# Supplies.net
KiCad netlist of a schematic drawn in Altium Designer
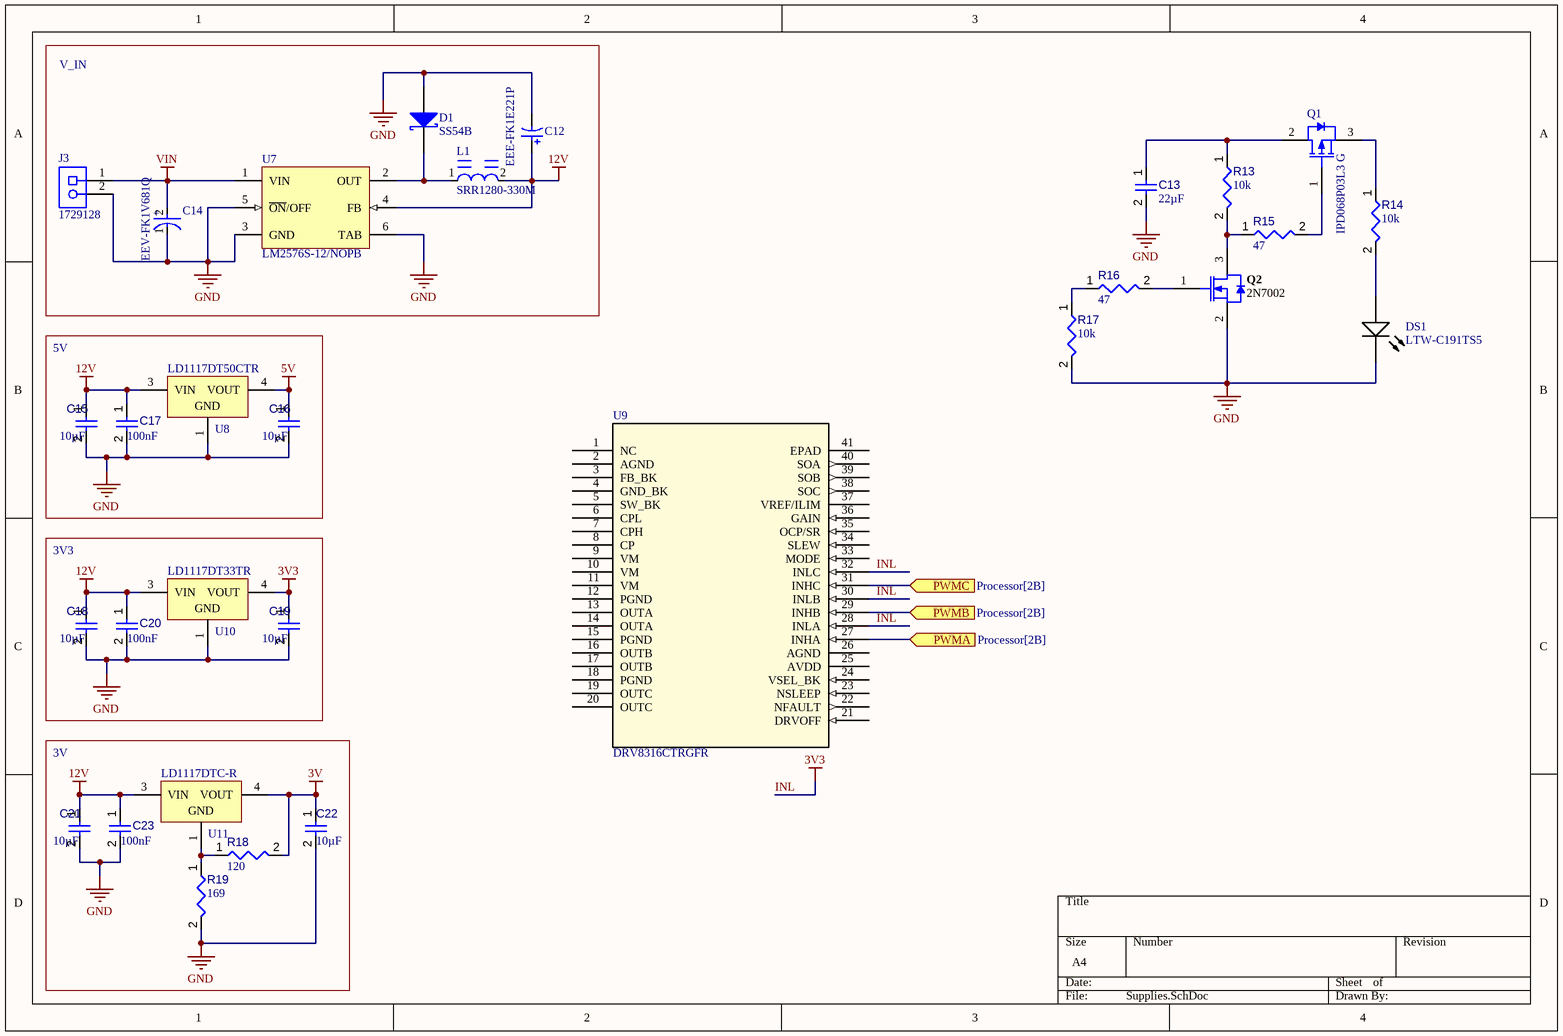
[diagram p0: Supplies.SchDoc]

(export (version "E")
  (design (tool "Eeschema 10.0.6"))
  (components
    (comp (ref "C12")
      (value "EEE-FK1E221P")
      (footprint "PNSC-EEE-FK1E221P_N")
      (fields (field (name "MANUFACTURER") "Panasonic"))
      (libsource (lib "Altium Content Vault") (part "CAP-P-2"))
    )
    (comp (ref "C13")
      (value "22µF")
      (footprint "CAPC0805(2012)145_L")
      (description "Chip Capacitor, 22µF +/-40%, 16V, 0805, Thickness 1.45 mm")
      (fields (field (name "TOLERANCE") "5%") (field (name "Comment") "Capacitor 22µF +/-40% 16V 0805"))
      (libsource (lib "UdeA") (part "CAP-NP-2"))
    )
    (comp (ref "C14")
      (value "EEV-FK1V681Q")
      (footprint "FP-FKH13-MFG")
      (description "CAP ALUM 680UF 20% 35V SMD")
      (fields (field (name "VOLTAGE") "35V") (field (name "TOLERANCE") "20%"))
      (libsource (lib "Altium Content Vault") (part "203bc49f2ac43e59fd269a8c329ed05"))
    )
    (comp (ref "C15")
      (value "10µF")
      (footprint "CAPC0805(2012)145_L")
      (description "Chip Capacitor, 22µF +/-40%, 16V, 0805, Thickness 1.45 mm")
      (fields (field (name "TOLERANCE") "5%") (field (name "Comment") "Capacitor 22µF +/-40% 16V 0805"))
      (libsource (lib "UdeA") (part "CAP-NP-2"))
    )
    (comp (ref "C16")
      (value "10µF")
      (footprint "CAPC0805(2012)145_L")
      (description "Chip Capacitor, 22µF +/-40%, 16V, 0805, Thickness 1.45 mm")
      (fields (field (name "TOLERANCE") "5%") (field (name "Comment") "Capacitor 22µF +/-40% 16V 0805"))
      (libsource (lib "UdeA") (part "CAP-NP-2"))
    )
    (comp (ref "C17")
      (value "100nF")
      (footprint "CAPC1608X90X40NL10T20")
      (description "Chip Capacitor, 100 nF, +/- 10%, 50 V, 0603 (1608 Metric)")
      (fields (field (name "TOLERANCE") "10%") (field (name "Comment") "Capacitor 100 nF +/-10% 50 V 0603"))
      (libsource (lib "UdeA") (part "CAP-NP-2"))
    )
    (comp (ref "C18")
      (value "10µF")
      (footprint "CAPC0805(2012)145_L")
      (description "Chip Capacitor, 22µF +/-40%, 16V, 0805, Thickness 1.45 mm")
      (fields (field (name "TOLERANCE") "5%") (field (name "Comment") "Capacitor 22µF +/-40% 16V 0805"))
      (libsource (lib "UdeA") (part "CAP-NP-2"))
    )
    (comp (ref "C19")
      (value "10µF")
      (footprint "CAPC0805(2012)145_L")
      (description "Chip Capacitor, 22µF +/-40%, 16V, 0805, Thickness 1.45 mm")
      (fields (field (name "TOLERANCE") "5%") (field (name "Comment") "Capacitor 22µF +/-40% 16V 0805"))
      (libsource (lib "UdeA") (part "CAP-NP-2"))
    )
    (comp (ref "C20")
      (value "100nF")
      (footprint "CAPC1608X90X40NL10T20")
      (description "Chip Capacitor, 100 nF, +/- 10%, 50 V, 0603 (1608 Metric)")
      (fields (field (name "TOLERANCE") "10%") (field (name "Comment") "Capacitor 100 nF +/-10% 50 V 0603"))
      (libsource (lib "UdeA") (part "CAP-NP-2"))
    )
    (comp (ref "C21")
      (value "10µF")
      (footprint "CAPC0805(2012)145_L")
      (description "Chip Capacitor, 22µF +/-40%, 16V, 0805, Thickness 1.45 mm")
      (fields (field (name "TOLERANCE") "5%") (field (name "Comment") "Capacitor 22µF +/-40% 16V 0805"))
      (libsource (lib "UdeA") (part "CAP-NP-2"))
    )
    (comp (ref "C22")
      (value "10µF")
      (footprint "CAPC0805(2012)145_L")
      (description "Chip Capacitor, 22µF +/-40%, 16V, 0805, Thickness 1.45 mm")
      (fields (field (name "TOLERANCE") "5%") (field (name "Comment") "Capacitor 22µF +/-40% 16V 0805"))
      (libsource (lib "UdeA") (part "CAP-NP-2"))
    )
    (comp (ref "C23")
      (value "100nF")
      (footprint "CAPC1608X90X40NL10T20")
      (description "Chip Capacitor, 100 nF, +/- 10%, 50 V, 0603 (1608 Metric)")
      (fields (field (name "TOLERANCE") "10%") (field (name "Comment") "Capacitor 100 nF +/-10% 50 V 0603"))
      (libsource (lib "UdeA") (part "CAP-NP-2"))
    )
    (comp (ref "D1")
      (value "SS54B")
      (footprint "JCET-SMB-2_M")
      (description "Schottky Barrier Rectifier, 40 V, 5 A, -55 to 150 degC, 2-Pin SMD")
      (fields (field (name "MANUFACTURER") "JCET"))
      (libsource (lib "Altium Content Vault") (part "DSKY-AK-2"))
    )
    (comp (ref "DS1")
      (value "LTW-C191TS5")
      (footprint "LTST-LTW-C191TS5_V")
      (description "LED Uni-Color White, 70 mW, 20 mA, -20 to 80 degC, 2-Pin SMD, RoHS, Tape and Reel")
      (fields (field (name "POWER") "70mW") (field (name "MANUFACTURER") "Lite-On"))
      (libsource (lib "UdeA") (part "LED-WHITE-AK-2"))
    )
    (comp (ref "J3")
      (value "1729128")
      (footprint "PHOE-1729128-2_V")
      (description "PCB Terminal Block, 13.5 A, 400 V, 2-Pin THD, RoHS, Bulk")
      (fields (field (name "MANUFACTURER") "Phoenix Contact"))
      (libsource (lib "Altium Content Vault") (part "CN-2P-F-R2"))
    )
    (comp (ref "L1")
      (value "SRR1280-330M")
      (footprint "FP-SRR1280-MFG")
      (description "FIXED IND 33UH 3.5A 57 MOHM SMD")
      (fields (field (name "TOLERANCE") "20%"))
      (libsource (lib "Altium Content Vault") (part "6d0fbef048cab01dc475e6ab11ab505"))
    )
    (comp (ref "Q1")
      (value "IPD068P03L3 G")
      (footprint "INF-PG-TO252-3-1_L")
      (fields (field (name "MANUFACTURER") "Infineon"))
      (libsource (lib "Altium Content Vault") (part "INF-PEMOS-GDS-3"))
    )
    (comp (ref "Q2")
      (value "2N7002")
      (footprint "INF-PG-SOT23_M")
      (fields (field (name "MANUFACTURER") "Infineon"))
      (libsource (lib "Altium Content Vault") (part "INF-NDMOS-GSD-3"))
    )
    (comp (ref "R13")
      (value "10k")
      (footprint "RESC1608X55X25ML10T15")
      (description "Chip Resistor, 10 KOhm, +/- 1%, 01 W, -55 to 155 degC, 0603 (1608 Metric)")
      (fields (field (name "POWER") "100mW") (field (name "TOLERANCE") "1%"))
      (libsource (lib "UdeA") (part "RES-2"))
    )
    (comp (ref "R14")
      (value "10k")
      (footprint "RESC1608X55X25ML10T15")
      (description "Chip Resistor, 10 KOhm, +/- 1%, 01 W, -55 to 155 degC, 0603 (1608 Metric)")
      (fields (field (name "POWER") "100mW") (field (name "TOLERANCE") "1%"))
      (libsource (lib "UdeA") (part "RES-2"))
    )
    (comp (ref "R15")
      (value "47")
      (footprint "RESC1608X55X25ML10T15")
      (description "Chip Resistor, 10 KOhm, +/- 1%, 01 W, -55 to 155 degC, 0603 (1608 Metric)")
      (fields (field (name "POWER") "100mW") (field (name "TOLERANCE") "1%"))
      (libsource (lib "UdeA") (part "RES-2"))
    )
    (comp (ref "R16")
      (value "47")
      (footprint "RESC1608X55X25ML10T15")
      (description "Chip Resistor, 10 KOhm, +/- 1%, 01 W, -55 to 155 degC, 0603 (1608 Metric)")
      (fields (field (name "POWER") "100mW") (field (name "TOLERANCE") "1%"))
      (libsource (lib "UdeA") (part "RES-2"))
    )
    (comp (ref "R17")
      (value "10k")
      (footprint "RESC1608X55X25ML10T15")
      (description "Chip Resistor, 10 KOhm, +/- 1%, 01 W, -55 to 155 degC, 0603 (1608 Metric)")
      (fields (field (name "POWER") "100mW") (field (name "TOLERANCE") "1%"))
      (libsource (lib "UdeA") (part "RES-2"))
    )
    (comp (ref "R18")
      (value "120")
      (footprint "RESC1608X55X25ML10T15")
      (description "Chip Resistor, 10 KOhm, +/- 1%, 01 W, -55 to 155 degC, 0603 (1608 Metric)")
      (fields (field (name "POWER") "100mW") (field (name "TOLERANCE") "1%"))
      (libsource (lib "UdeA") (part "RES-2"))
    )
    (comp (ref "R19")
      (value "169")
      (footprint "RESC1608X55X25ML10T15")
      (description "Chip Resistor, 10 KOhm, +/- 1%, 01 W, -55 to 155 degC, 0603 (1608 Metric)")
      (fields (field (name "POWER") "100mW") (field (name "TOLERANCE") "1%"))
      (libsource (lib "UdeA") (part "RES-2"))
    )
    (comp (ref "U7")
      (value "LM2576S-12/NOPB")
      (footprint "KTT0005B_N")
      (description "SIMPLE SWITCHER® 3A Step-Down Voltage Regulator, 5-pin TO-263, Pb-Free")
      (fields (field (name "MANUFACTURER") "Texas Instruments"))
      (libsource (lib "Altium Content Vault") (part "PM-REG-LM2575HVS-12"))
    )
    (comp (ref "U8")
      (value "LD1117DT50CTR")
      (footprint "TO-252_N")
      (description "Fixed Low Drop Positive Voltage Regulator, 5V, 3-Pin DPAK, Tape and Reel")
      (libsource (lib "Altium Content Vault") (part "PM-REG-LD1117-SOT3"))
    )
    (comp (ref "U9")
      (value "DRV8316CTRGFR")
      (footprint "VQFN40_RGF_TEX")
      (description "No Description Available")
      (fields (field (name "COPYRIGHT") "Copyright (C) 2024 Ultra Librarian. All rights reserved."))
      (libsource (lib "DRV8316CTRGFR") (part "DRV8316CTRGFR"))
    )
    (comp (ref "U10")
      (value "LD1117DT33TR")
      (footprint "TO-252_N")
      (description "Fixed Low Drop Positive Voltage Regulator, 3.3V, 3-Pin DPAK, Tape and Reel")
      (libsource (lib "Altium Content Vault") (part "PM-REG-LD1117-SOT3"))
    )
    (comp (ref "U11")
      (value "LD1117DTC-R")
      (footprint "TO-252_M")
      (description "Adjustable Low Drop Voltage Regulator, 1.25 to 15V, 3-Pin DPAK, Tape and Reel")
      (libsource (lib "Altium Content Vault") (part "PM-REG-LD1117-SOT3"))
    )
  )
  (nets
    (net (code "1") (name "/PWMA") (class "Default")
      (node (ref "U9") (pin "27") (pinfunction "INHA_27") (pintype "input"))
    )
    (net (code "2") (name "/PWMB") (class "Default")
      (node (ref "U9") (pin "29") (pinfunction "INHB_29") (pintype "input"))
    )
    (net (code "3") (name "/PWMC") (class "Default")
      (node (ref "U9") (pin "31") (pinfunction "INHC_31") (pintype "input"))
    )
    (net (code "4") (name "3V") (class "Default")
      (node (ref "C22") (pin "1") (pinfunction "1_1") (pintype "passive"))
      (node (ref "R18") (pin "2") (pinfunction "2_2") (pintype "passive"))
      (node (ref "U11") (pin "4") (pinfunction "VOUT_4") (pintype "power_in"))
    )
    (net (code "5") (name "3V3") (class "Default")
      (node (ref "C19") (pin "1") (pinfunction "1_1") (pintype "passive"))
      (node (ref "U10") (pin "4") (pinfunction "VOUT_4") (pintype "power_in"))
      (node (ref "U9") (pin "28") (pinfunction "INLA_28") (pintype "input"))
      (node (ref "U9") (pin "30") (pinfunction "INLB_30") (pintype "input"))
      (node (ref "U9") (pin "32") (pinfunction "INLC_32") (pintype "input"))
    )
    (net (code "6") (name "5V") (class "Default")
      (node (ref "C16") (pin "1") (pinfunction "1_1") (pintype "passive"))
      (node (ref "U8") (pin "4") (pinfunction "VOUT_4") (pintype "power_in"))
    )
    (net (code "7") (name "12V") (class "Default")
      (node (ref "C12") (pin "1") (pinfunction "1_1") (pintype "passive"))
      (node (ref "C15") (pin "1") (pinfunction "1_1") (pintype "passive"))
      (node (ref "C17") (pin "1") (pinfunction "1_1") (pintype "passive"))
      (node (ref "C18") (pin "1") (pinfunction "1_1") (pintype "passive"))
      (node (ref "C20") (pin "1") (pinfunction "1_1") (pintype "passive"))
      (node (ref "C21") (pin "1") (pinfunction "1_1") (pintype "passive"))
      (node (ref "C23") (pin "1") (pinfunction "1_1") (pintype "passive"))
      (node (ref "L1") (pin "2") (pinfunction "2_2") (pintype "passive"))
      (node (ref "U10") (pin "3") (pinfunction "VIN_3") (pintype "power_in"))
      (node (ref "U11") (pin "3") (pinfunction "VIN_3") (pintype "power_in"))
      (node (ref "U7") (pin "4") (pinfunction "FB_4") (pintype "input"))
      (node (ref "U8") (pin "3") (pinfunction "VIN_3") (pintype "power_in"))
    )
    (net (code "8") (name "GND") (class "Default")
      (node (ref "C12") (pin "2") (pinfunction "2_2") (pintype "passive"))
      (node (ref "C13") (pin "2") (pinfunction "2_2") (pintype "passive"))
      (node (ref "C14") (pin "1") (pinfunction "C_1") (pintype "passive"))
      (node (ref "C15") (pin "2") (pinfunction "2_2") (pintype "passive"))
      (node (ref "C16") (pin "2") (pinfunction "2_2") (pintype "passive"))
      (node (ref "C17") (pin "2") (pinfunction "2_2") (pintype "passive"))
      (node (ref "C18") (pin "2") (pinfunction "2_2") (pintype "passive"))
      (node (ref "C19") (pin "2") (pinfunction "2_2") (pintype "passive"))
      (node (ref "C20") (pin "2") (pinfunction "2_2") (pintype "passive"))
      (node (ref "C21") (pin "2") (pinfunction "2_2") (pintype "passive"))
      (node (ref "C22") (pin "2") (pinfunction "2_2") (pintype "passive"))
      (node (ref "C23") (pin "2") (pinfunction "2_2") (pintype "passive"))
      (node (ref "D1") (pin "1") (pinfunction "A_1") (pintype "passive"))
      (node (ref "DS1") (pin "2") (pinfunction "K_2") (pintype "passive"))
      (node (ref "J3") (pin "2") (pinfunction "2_2") (pintype "passive"))
      (node (ref "Q2") (pin "2") (pinfunction "SOURCE_2") (pintype "passive"))
      (node (ref "R17") (pin "2") (pinfunction "2_2") (pintype "passive"))
      (node (ref "R19") (pin "2") (pinfunction "2_2") (pintype "passive"))
      (node (ref "U10") (pin "1") (pinfunction "GND_1") (pintype "power_in"))
      (node (ref "U7") (pin "3") (pinfunction "GND_3") (pintype "power_in"))
      (node (ref "U7") (pin "5") (pinfunction "~{ON}/OFF_5") (pintype "input"))
      (node (ref "U7") (pin "6") (pinfunction "TAB_6") (pintype "power_in"))
      (node (ref "U8") (pin "1") (pinfunction "GND_1") (pintype "power_in"))
    )
    (net (code "9") (name "Net-(D1-K)") (class "Default")
      (node (ref "D1") (pin "2") (pinfunction "K_2") (pintype "passive"))
      (node (ref "L1") (pin "1") (pinfunction "1_1") (pintype "passive"))
      (node (ref "U7") (pin "2") (pinfunction "OUT_2") (pintype "power_in"))
    )
    (net (code "10") (name "Net-(DS1-A)") (class "Default")
      (node (ref "DS1") (pin "1") (pinfunction "A_1") (pintype "passive"))
      (node (ref "R14") (pin "2") (pinfunction "2_2") (pintype "passive"))
    )
    (net (code "11") (name "Net-(Q1-DRAIN)") (class "Default")
      (node (ref "C13") (pin "1") (pinfunction "1_1") (pintype "passive"))
      (node (ref "Q1") (pin "2") (pinfunction "DRAIN_2") (pintype "passive"))
      (node (ref "R13") (pin "1") (pinfunction "1_1") (pintype "passive"))
    )
    (net (code "12") (name "Net-(Q1-GATE)") (class "Default")
      (node (ref "Q1") (pin "1") (pinfunction "GATE_1") (pintype "passive"))
      (node (ref "R15") (pin "2") (pinfunction "2_2") (pintype "passive"))
    )
    (net (code "13") (name "Net-(Q1-SOURCE)") (class "Default")
      (node (ref "Q1") (pin "3") (pinfunction "SOURCE_3") (pintype "passive"))
      (node (ref "R14") (pin "1") (pinfunction "1_1") (pintype "passive"))
    )
    (net (code "14") (name "Net-(Q2-DRAIN)") (class "Default")
      (node (ref "Q2") (pin "3") (pinfunction "DRAIN_3") (pintype "passive"))
      (node (ref "R13") (pin "2") (pinfunction "2_2") (pintype "passive"))
      (node (ref "R15") (pin "1") (pinfunction "1_1") (pintype "passive"))
    )
    (net (code "15") (name "Net-(Q2-GATE)") (class "Default")
      (node (ref "Q2") (pin "1") (pinfunction "GATE_1") (pintype "passive"))
      (node (ref "R16") (pin "2") (pinfunction "2_2") (pintype "passive"))
    )
    (net (code "16") (name "Net-(R16-Pad1)") (class "Default")
      (node (ref "R16") (pin "1") (pinfunction "1_1") (pintype "passive"))
      (node (ref "R17") (pin "1") (pinfunction "1_1") (pintype "passive"))
    )
    (net (code "17") (name "Net-(U11-GND)") (class "Default")
      (node (ref "R18") (pin "1") (pinfunction "1_1") (pintype "passive"))
      (node (ref "R19") (pin "1") (pinfunction "1_1") (pintype "passive"))
      (node (ref "U11") (pin "1") (pinfunction "GND_1") (pintype "power_in"))
    )
    (net (code "18") (name "VIN") (class "Default")
      (node (ref "C14") (pin "2") (pinfunction "A_2") (pintype "passive"))
      (node (ref "J3") (pin "1") (pinfunction "1_1") (pintype "passive"))
      (node (ref "U7") (pin "1") (pinfunction "VIN_1") (pintype "power_in"))
    )
    (net (code "19") (name "unconnected-(U9-AGND-Pad2)") (class "Default")
      (node (ref "U9") (pin "2") (pinfunction "AGND_2") (pintype "power_in"))
    )
    (net (code "20") (name "unconnected-(U9-AGND-Pad26)") (class "Default")
      (node (ref "U9") (pin "26") (pinfunction "AGND_26") (pintype "power_in"))
    )
    (net (code "21") (name "unconnected-(U9-AVDD-Pad25)") (class "Default")
      (node (ref "U9") (pin "25") (pinfunction "AVDD_25") (pintype "power_in"))
    )
    (net (code "22") (name "unconnected-(U9-CP-Pad8)") (class "Default")
      (node (ref "U9") (pin "8") (pinfunction "CP_8") (pintype "power_in"))
    )
    (net (code "23") (name "unconnected-(U9-CPH-Pad7)") (class "Default")
      (node (ref "U9") (pin "7") (pinfunction "CPH_7") (pintype "power_in"))
    )
    (net (code "24") (name "unconnected-(U9-CPL-Pad6)") (class "Default")
      (node (ref "U9") (pin "6") (pinfunction "CPL_6") (pintype "power_in"))
    )
    (net (code "25") (name "unconnected-(U9-DRVOFF-Pad21)") (class "Default")
      (node (ref "U9") (pin "21") (pinfunction "DRVOFF_21") (pintype "input"))
    )
    (net (code "26") (name "unconnected-(U9-EPAD-Pad41)") (class "Default")
      (node (ref "U9") (pin "41") (pinfunction "EPAD_41") (pintype "power_in"))
    )
    (net (code "27") (name "unconnected-(U9-FB_BK-Pad3)") (class "Default")
      (node (ref "U9") (pin "3") (pinfunction "FB_BK_3") (pintype "power_in"))
    )
    (net (code "28") (name "unconnected-(U9-GAIN-Pad36)") (class "Default")
      (node (ref "U9") (pin "36") (pinfunction "GAIN_36") (pintype "input"))
    )
    (net (code "29") (name "unconnected-(U9-GND_BK-Pad4)") (class "Default")
      (node (ref "U9") (pin "4") (pinfunction "GND_BK_4") (pintype "power_in"))
    )
    (net (code "30") (name "unconnected-(U9-MODE-Pad33)") (class "Default")
      (node (ref "U9") (pin "33") (pinfunction "MODE_33") (pintype "input"))
    )
    (net (code "31") (name "unconnected-(U9-NC-Pad1)") (class "Default")
      (node (ref "U9") (pin "1") (pinfunction "NC_1") (pintype "passive"))
    )
    (net (code "32") (name "unconnected-(U9-NFAULT-Pad22)") (class "Default")
      (node (ref "U9") (pin "22") (pinfunction "NFAULT_22") (pintype "output"))
    )
    (net (code "33") (name "unconnected-(U9-NSLEEP-Pad23)") (class "Default")
      (node (ref "U9") (pin "23") (pinfunction "NSLEEP_23") (pintype "input"))
    )
    (net (code "34") (name "unconnected-(U9-OCP{slash}SR-Pad35)") (class "Default")
      (node (ref "U9") (pin "35") (pinfunction "OCP/SR_35") (pintype "input"))
    )
    (net (code "35") (name "unconnected-(U9-OUTA-Pad13)") (class "Default")
      (node (ref "U9") (pin "13") (pinfunction "OUTA_13") (pintype "power_in"))
    )
    (net (code "36") (name "unconnected-(U9-OUTA-Pad14)") (class "Default")
      (node (ref "U9") (pin "14") (pinfunction "OUTA_14") (pintype "power_in"))
    )
    (net (code "37") (name "unconnected-(U9-OUTB-Pad16)") (class "Default")
      (node (ref "U9") (pin "16") (pinfunction "OUTB_16") (pintype "power_in"))
    )
    (net (code "38") (name "unconnected-(U9-OUTB-Pad17)") (class "Default")
      (node (ref "U9") (pin "17") (pinfunction "OUTB_17") (pintype "power_in"))
    )
    (net (code "39") (name "unconnected-(U9-OUTC-Pad19)") (class "Default")
      (node (ref "U9") (pin "19") (pinfunction "OUTC_19") (pintype "power_in"))
    )
    (net (code "40") (name "unconnected-(U9-OUTC-Pad20)") (class "Default")
      (node (ref "U9") (pin "20") (pinfunction "OUTC_20") (pintype "power_in"))
    )
    (net (code "41") (name "unconnected-(U9-PGND-Pad12)") (class "Default")
      (node (ref "U9") (pin "12") (pinfunction "PGND_12") (pintype "power_in"))
    )
    (net (code "42") (name "unconnected-(U9-PGND-Pad15)") (class "Default")
      (node (ref "U9") (pin "15") (pinfunction "PGND_15") (pintype "power_in"))
    )
    (net (code "43") (name "unconnected-(U9-PGND-Pad18)") (class "Default")
      (node (ref "U9") (pin "18") (pinfunction "PGND_18") (pintype "power_in"))
    )
    (net (code "44") (name "unconnected-(U9-SLEW-Pad34)") (class "Default")
      (node (ref "U9") (pin "34") (pinfunction "SLEW_34") (pintype "input"))
    )
    (net (code "45") (name "unconnected-(U9-SOA-Pad40)") (class "Default")
      (node (ref "U9") (pin "40") (pinfunction "SOA_40") (pintype "output"))
    )
    (net (code "46") (name "unconnected-(U9-SOB-Pad39)") (class "Default")
      (node (ref "U9") (pin "39") (pinfunction "SOB_39") (pintype "output"))
    )
    (net (code "47") (name "unconnected-(U9-SOC-Pad38)") (class "Default")
      (node (ref "U9") (pin "38") (pinfunction "SOC_38") (pintype "output"))
    )
    (net (code "48") (name "unconnected-(U9-SW_BK-Pad5)") (class "Default")
      (node (ref "U9") (pin "5") (pinfunction "SW_BK_5") (pintype "power_in"))
    )
    (net (code "49") (name "unconnected-(U9-VM-Pad9)") (class "Default")
      (node (ref "U9") (pin "9") (pinfunction "VM_9") (pintype "power_in"))
    )
    (net (code "50") (name "unconnected-(U9-VM-Pad10)") (class "Default")
      (node (ref "U9") (pin "10") (pinfunction "VM_10") (pintype "power_in"))
    )
    (net (code "51") (name "unconnected-(U9-VM-Pad11)") (class "Default")
      (node (ref "U9") (pin "11") (pinfunction "VM_11") (pintype "power_in"))
    )
    (net (code "52") (name "unconnected-(U9-VREF{slash}ILIM-Pad37)") (class "Default")
      (node (ref "U9") (pin "37") (pinfunction "VREF/ILIM_37") (pintype "power_in"))
    )
    (net (code "53") (name "unconnected-(U9-VSEL_BK-Pad24)") (class "Default")
      (node (ref "U9") (pin "24") (pinfunction "VSEL_BK_24") (pintype "input"))
    )
  )
)
